# GEWI-base.net
KiCad netlist of a schematic drawn in EAGLE
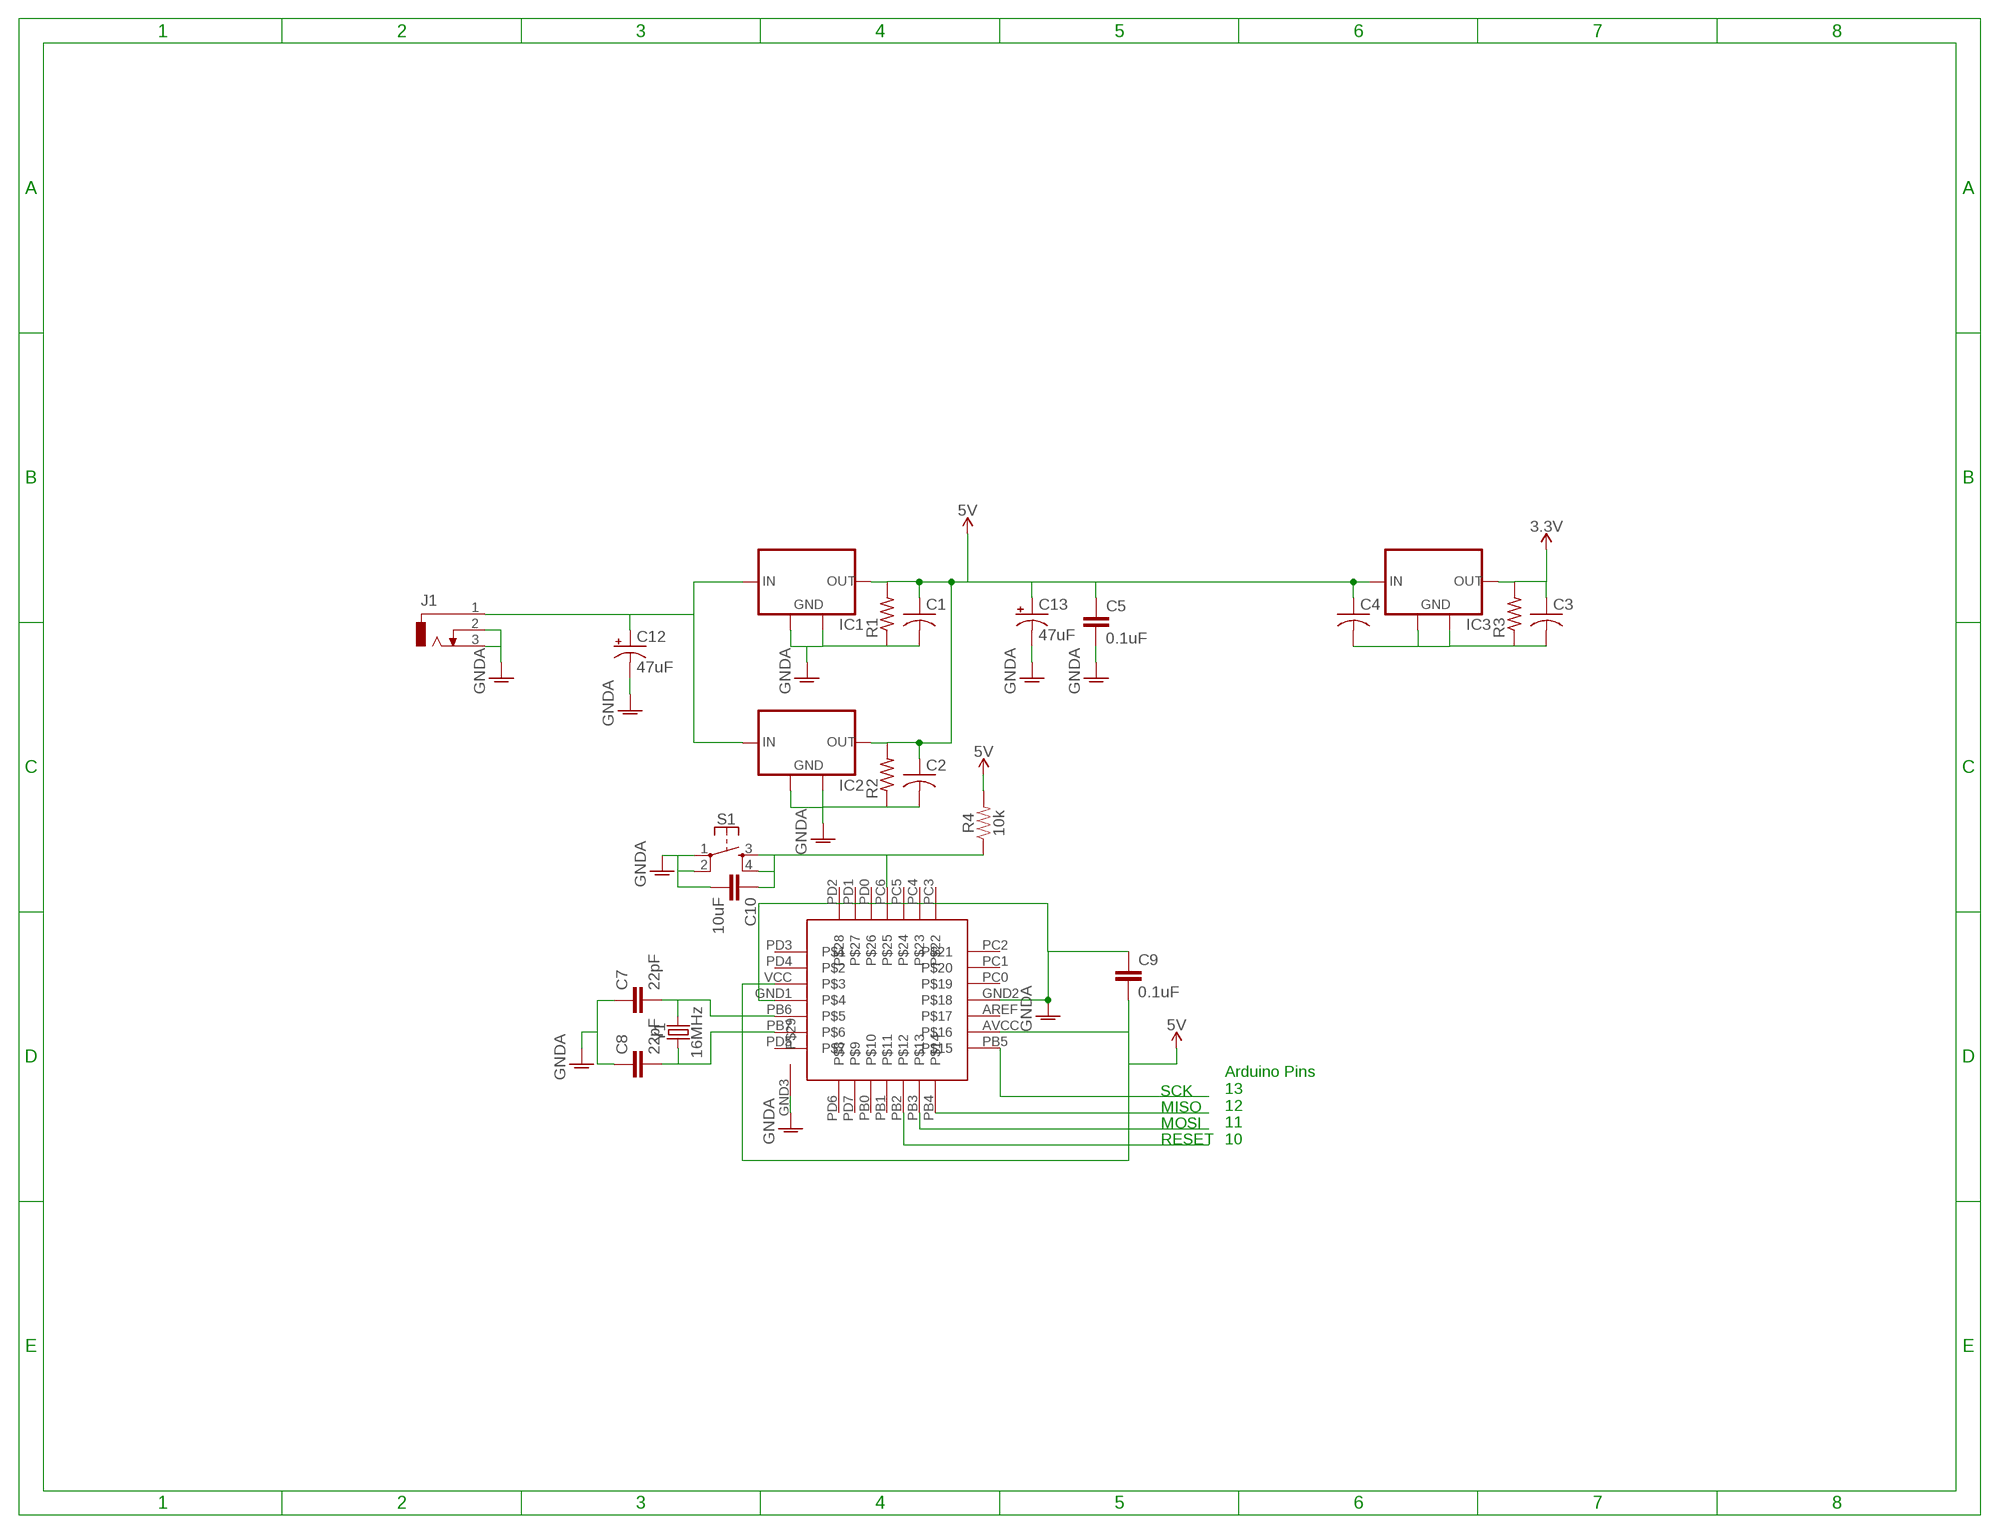
[diagram p0: schematic, sheet 1]

(export (version "E")
  (design (tool "Eeschema 10.0.6"))
  (components
    (comp (ref "C1")
      (value "C-USC0603")
      (footprint "eagle-import:C0603")
      (libsource (lib "eagle-import") (part "C-USC0603"))
    )
    (comp (ref "C2")
      (value "C-USC0603")
      (footprint "eagle-import:C0603")
      (libsource (lib "eagle-import") (part "C-USC0603"))
    )
    (comp (ref "C3")
      (value "C-USC0603")
      (footprint "eagle-import:C0603")
      (libsource (lib "eagle-import") (part "C-USC0603"))
    )
    (comp (ref "C4")
      (value "C-USC0603")
      (footprint "eagle-import:C0603")
      (libsource (lib "eagle-import") (part "C-USC0603"))
    )
    (comp (ref "C5")
      (value "0.1uF")
      (footprint "eagle-import:0603")
      (libsource (lib "eagle-import") (part "0.1UF-0603-25V-(+80/-20%)"))
    )
    (comp (ref "C7")
      (value "22pF")
      (footprint "eagle-import:0603")
      (libsource (lib "eagle-import") (part "22PF-0603-50V-5%"))
    )
    (comp (ref "C8")
      (value "22pF")
      (footprint "eagle-import:0603")
      (libsource (lib "eagle-import") (part "22PF-0603-50V-5%"))
    )
    (comp (ref "C9")
      (value "0.1uF")
      (footprint "eagle-import:0603")
      (libsource (lib "eagle-import") (part "0.1UF-0603-25V-(+80/-20%)"))
    )
    (comp (ref "C10")
      (value "10uF")
      (footprint "eagle-import:0603")
      (libsource (lib "eagle-import") (part "10UF-0603-6.3V-20%"))
    )
    (comp (ref "C12")
      (value "47uF")
      (footprint "eagle-import:PANASONIC_D")
      (libsource (lib "eagle-import") (part "47UF-POLAR-PANASONIC_D-35V-20%"))
    )
    (comp (ref "C13")
      (value "47uF")
      (footprint "eagle-import:PANASONIC_D")
      (libsource (lib "eagle-import") (part "47UF-POLAR-PANASONIC_D-35V-20%"))
    )
    (comp (ref "IC1")
      (value "MCP1825S-SOT223")
      (footprint "eagle-import:SOT223")
      (libsource (lib "eagle-import") (part "MCP1825S-SOT223"))
    )
    (comp (ref "IC2")
      (value "MCP1825S-SOT223")
      (footprint "eagle-import:SOT223")
      (libsource (lib "eagle-import") (part "MCP1825S-SOT223"))
    )
    (comp (ref "IC3")
      (value "MCP1825S-SOT223")
      (footprint "eagle-import:SOT223")
      (libsource (lib "eagle-import") (part "MCP1825S-SOT223"))
    )
    (comp (ref "J1")
      (value "DCJ0303")
      (footprint "eagle-import:DCJ0303")
      (libsource (lib "eagle-import") (part "DCJ0303"))
    )
    (comp (ref "R1")
      (value "R-US_R0603")
      (footprint "eagle-import:R0603")
      (libsource (lib "eagle-import") (part "R-US_R0603"))
    )
    (comp (ref "R2")
      (value "R-US_R0603")
      (footprint "eagle-import:R0603")
      (libsource (lib "eagle-import") (part "R-US_R0603"))
    )
    (comp (ref "R3")
      (value "R-US_R0603")
      (footprint "eagle-import:R0603")
      (libsource (lib "eagle-import") (part "R-US_R0603"))
    )
    (comp (ref "R4")
      (value "10k")
      (footprint "eagle-import:0603")
      (libsource (lib "eagle-import") (part "10KOHM-0603-1/10W-1%"))
    )
    (comp (ref "S1")
      (value "MOMENTARY-SWITCH-SPST-2-SMD-4.6X2.8MM")
      (footprint "eagle-import:TACTILE_SWITCH_SMD_4.6X2.8MM")
      (libsource (lib "eagle-import") (part "MOMENTARY-SWITCH-SPST-2-SMD-4.6X2.8MM"))
    )
    (comp (ref "U1")
      (value "ATMEGA328P-VQFN")
      (footprint "eagle-import:ATMEGA328P-VQFN")
      (libsource (lib "eagle-import") (part "ATMEGA328P-VQFN"))
    )
    (comp (ref "Y1")
      (value "16MHz")
      (footprint "eagle-import:CRYSTAL-SMD-5X3.2-4PAD")
      (libsource (lib "eagle-import") (part "CRYSTAL-16MHZSMD-5X3.2"))
    )
  )
  (nets
    (net (code "1") (name "/P$17") (class "Default")
      (node (ref "U1") (pin "AREF") (pinfunction "P$17_AREF") (pintype "power_in"))
    )
    (net (code "2") (name "3.3V") (class "Default")
      (node (ref "C3") (pin "1") (pinfunction "1_1") (pintype "passive"))
      (node (ref "IC3") (pin "3") (pinfunction "OUT_3") (pintype "output"))
      (node (ref "R3") (pin "2") (pinfunction "2_2") (pintype "passive"))
    )
    (net (code "3") (name "5V") (class "Default")
      (node (ref "C1") (pin "1") (pinfunction "1_1") (pintype "passive"))
      (node (ref "C13") (pin "+") (pinfunction "+_+") (pintype "passive"))
      (node (ref "C2") (pin "1") (pinfunction "1_1") (pintype "passive"))
      (node (ref "C4") (pin "1") (pinfunction "1_1") (pintype "passive"))
      (node (ref "C5") (pin "1") (pinfunction "1_1") (pintype "passive"))
      (node (ref "C9") (pin "2") (pinfunction "2_2") (pintype "passive"))
      (node (ref "IC1") (pin "3") (pinfunction "OUT_3") (pintype "output"))
      (node (ref "IC2") (pin "3") (pinfunction "OUT_3") (pintype "output"))
      (node (ref "IC3") (pin "1") (pinfunction "IN_1") (pintype "input"))
      (node (ref "R1") (pin "2") (pinfunction "2_2") (pintype "passive"))
      (node (ref "R2") (pin "2") (pinfunction "2_2") (pintype "passive"))
      (node (ref "R4") (pin "2") (pinfunction "2_2") (pintype "passive"))
      (node (ref "U1") (pin "AVCC") (pinfunction "P$16_AVCC") (pintype "power_in"))
      (node (ref "U1") (pin "VCC") (pinfunction "P$3_VCC") (pintype "power_in"))
    )
    (net (code "4") (name "GNDA") (class "Default")
      (node (ref "C1") (pin "2") (pinfunction "2_2") (pintype "passive"))
      (node (ref "C10") (pin "2") (pinfunction "2_2") (pintype "passive"))
      (node (ref "C12") (pin "-") (pinfunction "-_-") (pintype "passive"))
      (node (ref "C13") (pin "-") (pinfunction "-_-") (pintype "passive"))
      (node (ref "C2") (pin "2") (pinfunction "2_2") (pintype "passive"))
      (node (ref "C5") (pin "2") (pinfunction "2_2") (pintype "passive"))
      (node (ref "C7") (pin "1") (pinfunction "1_1") (pintype "passive"))
      (node (ref "C8") (pin "1") (pinfunction "1_1") (pintype "passive"))
      (node (ref "C9") (pin "1") (pinfunction "1_1") (pintype "passive"))
      (node (ref "IC1") (pin "2") (pinfunction "GND_2") (pintype "power_in"))
      (node (ref "IC1") (pin "4") (pinfunction "GND_4") (pintype "power_in"))
      (node (ref "IC2") (pin "2") (pinfunction "GND_2") (pintype "power_in"))
      (node (ref "IC2") (pin "4") (pinfunction "GND_4") (pintype "power_in"))
      (node (ref "J1") (pin "2") (pinfunction "2_2") (pintype "passive"))
      (node (ref "J1") (pin "3") (pinfunction "3_3") (pintype "passive"))
      (node (ref "R1") (pin "1") (pinfunction "1_1") (pintype "passive"))
      (node (ref "R2") (pin "1") (pinfunction "1_1") (pintype "passive"))
      (node (ref "S1") (pin "1") (pinfunction "1_1") (pintype "passive"))
      (node (ref "S1") (pin "2") (pinfunction "2_2") (pintype "passive"))
      (node (ref "U1") (pin "GND1") (pinfunction "P$4_GND1") (pintype "power_in"))
      (node (ref "U1") (pin "GND2") (pinfunction "P$18_GND2") (pintype "bidirectional"))
      (node (ref "U1") (pin "GND3") (pinfunction "P$29_GND3") (pintype "power_in"))
    )
    (net (code "5") (name "Net-(C3-Pad2)") (class "Default")
      (node (ref "C3") (pin "2") (pinfunction "2_2") (pintype "passive"))
      (node (ref "C4") (pin "2") (pinfunction "2_2") (pintype "passive"))
      (node (ref "IC3") (pin "2") (pinfunction "GND_2") (pintype "power_in"))
      (node (ref "IC3") (pin "4") (pinfunction "GND_4") (pintype "power_in"))
      (node (ref "R3") (pin "1") (pinfunction "1_1") (pintype "passive"))
    )
    (net (code "6") (name "Net-(IC1-IN)") (class "Default")
      (node (ref "C12") (pin "+") (pinfunction "+_+") (pintype "passive"))
      (node (ref "IC1") (pin "1") (pinfunction "IN_1") (pintype "input"))
      (node (ref "IC2") (pin "1") (pinfunction "IN_1") (pintype "input"))
      (node (ref "J1") (pin "1") (pinfunction "1_1") (pintype "passive"))
    )
    (net (code "7") (name "Net-(U1-P$5)") (class "Default")
      (node (ref "C7") (pin "2") (pinfunction "2_2") (pintype "passive"))
      (node (ref "U1") (pin "PB6") (pinfunction "P$5_PB6") (pintype "bidirectional"))
      (node (ref "Y1") (pin "3") (pinfunction "2_3") (pintype "passive"))
    )
    (net (code "8") (name "Net-(U1-P$6)") (class "Default")
      (node (ref "C8") (pin "2") (pinfunction "2_2") (pintype "passive"))
      (node (ref "U1") (pin "PB7") (pinfunction "P$6_PB7") (pintype "bidirectional"))
      (node (ref "Y1") (pin "1") (pinfunction "1_1") (pintype "passive"))
    )
    (net (code "9") (name "Net-(U1-P$25)") (class "Default")
      (node (ref "C10") (pin "1") (pinfunction "1_1") (pintype "passive"))
      (node (ref "R4") (pin "1") (pinfunction "1_1") (pintype "passive"))
      (node (ref "S1") (pin "3") (pinfunction "3_3") (pintype "passive"))
      (node (ref "S1") (pin "4") (pinfunction "4_4") (pintype "passive"))
      (node (ref "U1") (pin "PC6") (pinfunction "P$25_PC6") (pintype "bidirectional"))
    )
    (net (code "10") (name "unconnected-(U1-P$1-PadPD3)") (class "Default")
      (node (ref "U1") (pin "PD3") (pinfunction "P$1_PD3") (pintype "bidirectional"))
    )
    (net (code "11") (name "unconnected-(U1-P$2-PadPD4)") (class "Default")
      (node (ref "U1") (pin "PD4") (pinfunction "P$2_PD4") (pintype "bidirectional"))
    )
    (net (code "12") (name "unconnected-(U1-P$7-PadPD5)") (class "Default")
      (node (ref "U1") (pin "PD5") (pinfunction "P$7_PD5") (pintype "bidirectional"))
    )
    (net (code "13") (name "unconnected-(U1-P$8-PadPD6)") (class "Default")
      (node (ref "U1") (pin "PD6") (pinfunction "P$8_PD6") (pintype "bidirectional"))
    )
    (net (code "14") (name "unconnected-(U1-P$9-PadPD7)") (class "Default")
      (node (ref "U1") (pin "PD7") (pinfunction "P$9_PD7") (pintype "bidirectional"))
    )
    (net (code "15") (name "unconnected-(U1-P$10-PadPB0)") (class "Default")
      (node (ref "U1") (pin "PB0") (pinfunction "P$10_PB0") (pintype "bidirectional"))
    )
    (net (code "16") (name "unconnected-(U1-P$11-PadPB1)") (class "Default")
      (node (ref "U1") (pin "PB1") (pinfunction "P$11_PB1") (pintype "bidirectional"))
    )
    (net (code "17") (name "unconnected-(U1-P$12-PadPB2)") (class "Default")
      (node (ref "U1") (pin "PB2") (pinfunction "P$12_PB2") (pintype "bidirectional"))
    )
    (net (code "18") (name "unconnected-(U1-P$13-PadPB3)") (class "Default")
      (node (ref "U1") (pin "PB3") (pinfunction "P$13_PB3") (pintype "bidirectional"))
    )
    (net (code "19") (name "unconnected-(U1-P$14-PadPB4)") (class "Default")
      (node (ref "U1") (pin "PB4") (pinfunction "P$14_PB4") (pintype "bidirectional"))
    )
    (net (code "20") (name "unconnected-(U1-P$15-PadPB5)") (class "Default")
      (node (ref "U1") (pin "PB5") (pinfunction "P$15_PB5") (pintype "bidirectional"))
    )
    (net (code "21") (name "unconnected-(U1-P$19-PadPC0)") (class "Default")
      (node (ref "U1") (pin "PC0") (pinfunction "P$19_PC0") (pintype "bidirectional"))
    )
    (net (code "22") (name "unconnected-(U1-P$20-PadPC1)") (class "Default")
      (node (ref "U1") (pin "PC1") (pinfunction "P$20_PC1") (pintype "bidirectional"))
    )
    (net (code "23") (name "unconnected-(U1-P$21-PadPC2)") (class "Default")
      (node (ref "U1") (pin "PC2") (pinfunction "P$21_PC2") (pintype "bidirectional"))
    )
    (net (code "24") (name "unconnected-(U1-P$22-PadPC3)") (class "Default")
      (node (ref "U1") (pin "PC3") (pinfunction "P$22_PC3") (pintype "bidirectional"))
    )
    (net (code "25") (name "unconnected-(U1-P$23-PadPC4)") (class "Default")
      (node (ref "U1") (pin "PC4") (pinfunction "P$23_PC4") (pintype "bidirectional"))
    )
    (net (code "26") (name "unconnected-(U1-P$24-PadPC5)") (class "Default")
      (node (ref "U1") (pin "PC5") (pinfunction "P$24_PC5") (pintype "bidirectional"))
    )
    (net (code "27") (name "unconnected-(U1-P$26-PadPD0)") (class "Default")
      (node (ref "U1") (pin "PD0") (pinfunction "P$26_PD0") (pintype "bidirectional"))
    )
    (net (code "28") (name "unconnected-(U1-P$27-PadPD1)") (class "Default")
      (node (ref "U1") (pin "PD1") (pinfunction "P$27_PD1") (pintype "bidirectional"))
    )
    (net (code "29") (name "unconnected-(U1-P$28-PadPD2)") (class "Default")
      (node (ref "U1") (pin "PD2") (pinfunction "P$28_PD2") (pintype "bidirectional"))
    )
  )
)
